# E-P-020-R1_0.net
KiCad netlist of a schematic drawn in EAGLE
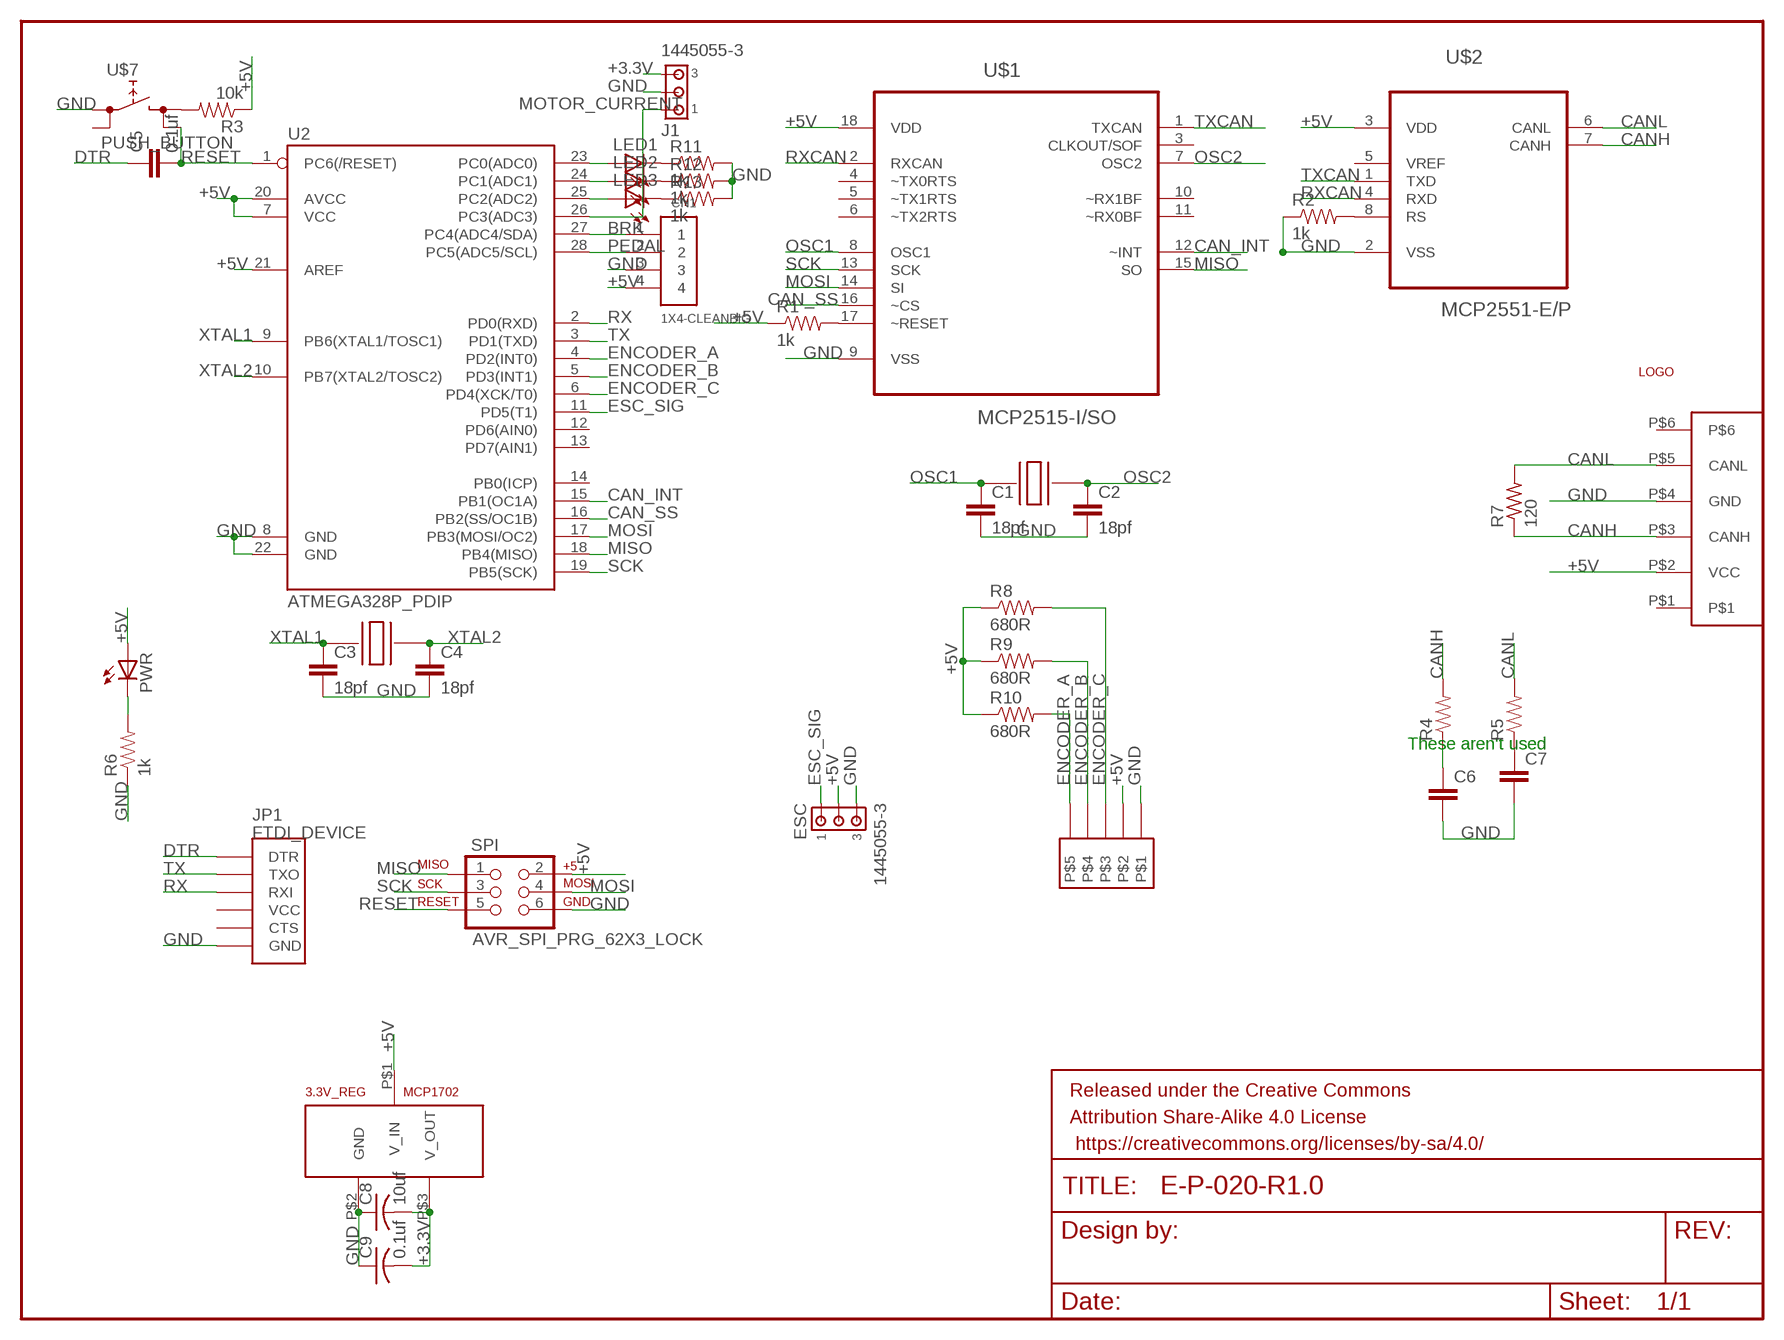
[diagram p0: schematic, sheet 1]

(export (version "E")
  (design (tool "Eeschema 10.0.6"))
  (components
    (comp (ref "3.3V_REG")
      (value "MCP1702")
      (footprint "eagle-import:SOT-23A")
      (libsource (lib "eagle-import") (part "MCP1702"))
    )
    (comp (ref "C1")
      (value "18pf")
      (footprint "eagle-import:0805")
      (libsource (lib "eagle-import") (part "CAP0805"))
    )
    (comp (ref "C2")
      (value "18pf")
      (footprint "eagle-import:0805")
      (libsource (lib "eagle-import") (part "CAP0805"))
    )
    (comp (ref "C3")
      (value "18pf")
      (footprint "eagle-import:0805")
      (libsource (lib "eagle-import") (part "CAP0805"))
    )
    (comp (ref "C4")
      (value "18pf")
      (footprint "eagle-import:0805")
      (libsource (lib "eagle-import") (part "CAP0805"))
    )
    (comp (ref "C5")
      (value "0.1uf")
      (footprint "eagle-import:0805")
      (libsource (lib "eagle-import") (part "CAP0805"))
    )
    (comp (ref "C6")
      (value "CAP0805")
      (footprint "eagle-import:0805")
      (libsource (lib "eagle-import") (part "CAP0805"))
    )
    (comp (ref "C7")
      (value "CAP0805")
      (footprint "eagle-import:0805")
      (libsource (lib "eagle-import") (part "CAP0805"))
    )
    (comp (ref "C8")
      (value "10uf")
      (footprint "eagle-import:C0805")
      (libsource (lib "eagle-import") (part "C-USC0805"))
    )
    (comp (ref "C9")
      (value "0.1uf")
      (footprint "eagle-import:C0805")
      (libsource (lib "eagle-import") (part "C-USC0805"))
    )
    (comp (ref "CAN-BUS")
      (value "CAN_6P6C")
      (footprint "eagle-import:CAN_6P6C")
      (libsource (lib "eagle-import") (part "CAN_6P6C"))
    )
    (comp (ref "CN1")
      (value "1X4-CLEANBIG")
      (footprint "eagle-import:1X04-CLEANBIG")
      (libsource (lib "eagle-import") (part "1X4-CLEANBIG"))
    )
    (comp (ref "ENCODER")
      (value "5_PIN_MICRO_MATE_N_LOCK")
      (footprint "eagle-import:5_PIN_MICRO_MATE_N_LOCK")
      (libsource (lib "eagle-import") (part "5_PIN_MICRO_MATE_N_LOCK"))
    )
    (comp (ref "ESC")
      (value "1445055-3")
      (footprint "eagle-import:1445055-3")
      (libsource (lib "eagle-import") (part "1445055-3"))
    )
    (comp (ref "FRAME1")
      (value "FRAME-LETTERNO_PACKAGE")
      (footprint "eagle-import:DUMMY")
      (fields (field (name "DESIGNER") "Nobody"))
      (libsource (lib "eagle-import") (part "FRAME-LETTERNO_PACKAGE"))
    )
    (comp (ref "J1")
      (value "1445055-3")
      (footprint "eagle-import:1445055-3")
      (libsource (lib "eagle-import") (part "1445055-3"))
    )
    (comp (ref "JP1")
      (value "FTDI_DEVICE")
      (footprint "eagle-import:FTDI_DEVICE_SIDE")
      (libsource (lib "eagle-import") (part "FTDI_DEVICE"))
    )
    (comp (ref "LED1")
      (value "LEDSMT1206")
      (footprint "eagle-import:1206")
      (libsource (lib "eagle-import") (part "adafruit_LEDSMT1206"))
    )
    (comp (ref "LED2")
      (value "LEDSMT1206")
      (footprint "eagle-import:1206")
      (libsource (lib "eagle-import") (part "adafruit_LEDSMT1206"))
    )
    (comp (ref "LED3")
      (value "LEDSMT1206")
      (footprint "eagle-import:1206")
      (libsource (lib "eagle-import") (part "adafruit_LEDSMT1206"))
    )
    (comp (ref "PWR")
      (value "LEDCHIPLED_1206")
      (footprint "eagle-import:CHIPLED_1206")
      (libsource (lib "eagle-import") (part "LEDCHIPLED_1206"))
    )
    (comp (ref "R1")
      (value "1k")
      (footprint "eagle-import:0805")
      (libsource (lib "eagle-import") (part "SparkFun-Passives_RESISTOR0805-RES"))
    )
    (comp (ref "R2")
      (value "1k")
      (footprint "eagle-import:0805")
      (libsource (lib "eagle-import") (part "SparkFun-Passives_RESISTOR0805-RES"))
    )
    (comp (ref "R3")
      (value "10k")
      (footprint "eagle-import:0805")
      (libsource (lib "eagle-import") (part "SparkFun-Passives_RESISTOR0805-RES"))
    )
    (comp (ref "R4")
      (value "RESISTOR0805-RES")
      (footprint "eagle-import:0805")
      (libsource (lib "eagle-import") (part "SparkFun-Passives_RESISTOR0805-RES"))
    )
    (comp (ref "R5")
      (value "RESISTOR0805-RES")
      (footprint "eagle-import:0805")
      (libsource (lib "eagle-import") (part "SparkFun-Passives_RESISTOR0805-RES"))
    )
    (comp (ref "R6")
      (value "1k")
      (footprint "eagle-import:0805")
      (libsource (lib "eagle-import") (part "SparkFun-Passives_RESISTOR0805-RES"))
    )
    (comp (ref "R7")
      (value "120")
      (footprint "eagle-import:M1206")
      (libsource (lib "eagle-import") (part "R-US_M1206"))
    )
    (comp (ref "R8")
      (value "680R")
      (footprint "eagle-import:0805")
      (libsource (lib "eagle-import") (part "0.75OHM-1/4W-1%(0805)"))
    )
    (comp (ref "R9")
      (value "680R")
      (footprint "eagle-import:0805")
      (libsource (lib "eagle-import") (part "0.75OHM-1/4W-1%(0805)"))
    )
    (comp (ref "R10")
      (value "680R")
      (footprint "eagle-import:0805")
      (libsource (lib "eagle-import") (part "0.75OHM-1/4W-1%(0805)"))
    )
    (comp (ref "R11")
      (value "1k")
      (footprint "eagle-import:0805")
      (libsource (lib "eagle-import") (part "RESISTOR0805-RES"))
    )
    (comp (ref "R12")
      (value "1k")
      (footprint "eagle-import:0805")
      (libsource (lib "eagle-import") (part "RESISTOR0805-RES"))
    )
    (comp (ref "R13")
      (value "1k")
      (footprint "eagle-import:0805")
      (libsource (lib "eagle-import") (part "RESISTOR0805-RES"))
    )
    (comp (ref "SPI")
      (value "AVR_SPI_PRG_62X3_LOCK")
      (footprint "eagle-import:2X3_LOCK")
      (libsource (lib "eagle-import") (part "AVR_SPI_PRG_62X3_LOCK"))
    )
    (comp (ref "U$1")
      (value "MCP2515-I/SO")
      (footprint "eagle-import:SOIC127P1034X264-18N")
      (libsource (lib "eagle-import") (part "MCP2515-I/SO"))
    )
    (comp (ref "U$2")
      (value "MCP2551-E/P")
      (footprint "eagle-import:DIP254P762X432-8")
      (libsource (lib "eagle-import") (part "MCP2551-E/P"))
    )
    (comp (ref "U$3")
      (value "CRYSTAL")
      (footprint "eagle-import:7A_CRYSTAL")
      (libsource (lib "eagle-import") (part "CRYSTAL"))
    )
    (comp (ref "U$4")
      (value "CRYSTAL")
      (footprint "eagle-import:7A_CRYSTAL")
      (libsource (lib "eagle-import") (part "CRYSTAL"))
    )
    (comp (ref "U$6")
      (value "LOGO")
      (footprint "eagle-import:LOGO")
      (libsource (lib "eagle-import") (part "LOGO"))
    )
    (comp (ref "U$7")
      (value "PUSH_BUTTON")
      (footprint "eagle-import:PUSHBUTTON")
      (libsource (lib "eagle-import") (part "PUSH_BUTTON"))
    )
    (comp (ref "U2")
      (value "ATMEGA328P_PDIP")
      (footprint "eagle-import:DIL28-3")
      (libsource (lib "eagle-import") (part "ATMEGA328P_PDIP"))
    )
  )
  (nets
    (net (code "1") (name "/+3.3V") (class "Default")
      (node (ref "3.3V_REG") (pin "P$3") (pinfunction "V_OUT_P$3") (pintype "bidirectional"))
      (node (ref "C8") (pin "2") (pinfunction "2_2") (pintype "passive"))
      (node (ref "C9") (pin "2") (pinfunction "2_2") (pintype "passive"))
      (node (ref "J1") (pin "3") (pinfunction "3_3") (pintype "passive"))
    )
    (net (code "2") (name "/+5V") (class "Default")
      (node (ref "3.3V_REG") (pin "P$1") (pinfunction "V_IN_P$1") (pintype "bidirectional"))
      (node (ref "CAN-BUS") (pin "P$2") (pinfunction "VCC_P$2") (pintype "bidirectional"))
      (node (ref "CN1") (pin "4") (pinfunction "4_4") (pintype "bidirectional"))
      (node (ref "ENCODER") (pin "P$4") (pinfunction "P$2_P$4") (pintype "bidirectional"))
      (node (ref "ESC") (pin "2") (pinfunction "2_2") (pintype "passive"))
      (node (ref "PWR") (pin "A") (pinfunction "A_A") (pintype "passive"))
      (node (ref "R1") (pin "1") (pinfunction "1_1") (pintype "passive"))
      (node (ref "R10") (pin "1") (pinfunction "1_1") (pintype "passive"))
      (node (ref "R3") (pin "1") (pinfunction "1_1") (pintype "passive"))
      (node (ref "R8") (pin "1") (pinfunction "1_1") (pintype "passive"))
      (node (ref "R9") (pin "1") (pinfunction "1_1") (pintype "passive"))
      (node (ref "SPI") (pin "2") (pinfunction "2_2") (pintype "passive"))
      (node (ref "U$1") (pin "18") (pinfunction "VDD_18") (pintype "power_in"))
      (node (ref "U$2") (pin "3") (pinfunction "VDD_3") (pintype "power_in"))
      (node (ref "U2") (pin "20") (pinfunction "AVCC_20") (pintype "bidirectional"))
      (node (ref "U2") (pin "21") (pinfunction "AREF_21") (pintype "bidirectional"))
      (node (ref "U2") (pin "7") (pinfunction "VCC_7") (pintype "bidirectional"))
    )
    (net (code "3") (name "/BRK") (class "Default")
      (node (ref "CN1") (pin "1") (pinfunction "1_1") (pintype "bidirectional"))
      (node (ref "U2") (pin "27") (pinfunction "PC4(ADC4/SDA)_27") (pintype "bidirectional"))
    )
    (net (code "4") (name "/CANH") (class "Default")
      (node (ref "CAN-BUS") (pin "P$3") (pinfunction "CANH_P$3") (pintype "bidirectional"))
      (node (ref "R4") (pin "2") (pinfunction "2_2") (pintype "passive"))
      (node (ref "R7") (pin "1") (pinfunction "1_1") (pintype "passive"))
      (node (ref "U$2") (pin "7") (pinfunction "CANH_7") (pintype "output"))
    )
    (net (code "5") (name "/CANL") (class "Default")
      (node (ref "CAN-BUS") (pin "P$5") (pinfunction "CANL_P$5") (pintype "bidirectional"))
      (node (ref "R5") (pin "2") (pinfunction "2_2") (pintype "passive"))
      (node (ref "R7") (pin "2") (pinfunction "2_2") (pintype "passive"))
      (node (ref "U$2") (pin "6") (pinfunction "CANL_6") (pintype "output"))
    )
    (net (code "6") (name "/CAN_INT") (class "Default")
      (node (ref "U$1") (pin "12") (pinfunction "~{INT}_12") (pintype "output"))
      (node (ref "U2") (pin "15") (pinfunction "PB1(OC1A)_15") (pintype "bidirectional"))
    )
    (net (code "7") (name "/CAN_SS") (class "Default")
      (node (ref "U$1") (pin "16") (pinfunction "~{CS}_16") (pintype "input"))
      (node (ref "U2") (pin "16") (pinfunction "PB2(SS/OC1B)_16") (pintype "bidirectional"))
    )
    (net (code "8") (name "/DTR") (class "Default")
      (node (ref "C5") (pin "1") (pinfunction "1_1") (pintype "passive"))
      (node (ref "JP1") (pin "P$1") (pinfunction "DTR_P$1") (pintype "bidirectional"))
    )
    (net (code "9") (name "/ENCODER_A") (class "Default")
      (node (ref "ENCODER") (pin "P$1") (pinfunction "P$5_P$1") (pintype "bidirectional"))
      (node (ref "R10") (pin "2") (pinfunction "2_2") (pintype "passive"))
      (node (ref "U2") (pin "4") (pinfunction "PD2(INT0)_4") (pintype "bidirectional"))
    )
    (net (code "10") (name "/ENCODER_B") (class "Default")
      (node (ref "ENCODER") (pin "P$2") (pinfunction "P$4_P$2") (pintype "bidirectional"))
      (node (ref "R9") (pin "2") (pinfunction "2_2") (pintype "passive"))
      (node (ref "U2") (pin "5") (pinfunction "PD3(INT1)_5") (pintype "bidirectional"))
    )
    (net (code "11") (name "/ENCODER_C") (class "Default")
      (node (ref "ENCODER") (pin "P$3") (pinfunction "P$3_P$3") (pintype "bidirectional"))
      (node (ref "R8") (pin "2") (pinfunction "2_2") (pintype "passive"))
      (node (ref "U2") (pin "6") (pinfunction "PD4(XCK/T0)_6") (pintype "bidirectional"))
    )
    (net (code "12") (name "/ESC_SIG") (class "Default")
      (node (ref "ESC") (pin "1") (pinfunction "1_1") (pintype "passive"))
      (node (ref "U2") (pin "11") (pinfunction "PD5(T1)_11") (pintype "bidirectional"))
    )
    (net (code "13") (name "/GND") (class "Default")
      (node (ref "3.3V_REG") (pin "P$2") (pinfunction "GND_P$2") (pintype "bidirectional"))
      (node (ref "C1") (pin "2") (pinfunction "2_2") (pintype "passive"))
      (node (ref "C2") (pin "2") (pinfunction "2_2") (pintype "passive"))
      (node (ref "C3") (pin "2") (pinfunction "2_2") (pintype "passive"))
      (node (ref "C4") (pin "2") (pinfunction "2_2") (pintype "passive"))
      (node (ref "C6") (pin "2") (pinfunction "2_2") (pintype "passive"))
      (node (ref "C7") (pin "2") (pinfunction "2_2") (pintype "passive"))
      (node (ref "C8") (pin "1") (pinfunction "1_1") (pintype "passive"))
      (node (ref "C9") (pin "1") (pinfunction "1_1") (pintype "passive"))
      (node (ref "CAN-BUS") (pin "P$4") (pinfunction "GND_P$4") (pintype "bidirectional"))
      (node (ref "CN1") (pin "3") (pinfunction "3_3") (pintype "bidirectional"))
      (node (ref "ENCODER") (pin "P$5") (pinfunction "P$1_P$5") (pintype "bidirectional"))
      (node (ref "ESC") (pin "3") (pinfunction "3_3") (pintype "passive"))
      (node (ref "J1") (pin "2") (pinfunction "2_2") (pintype "passive"))
      (node (ref "JP1") (pin "P$6") (pinfunction "GND_P$6") (pintype "bidirectional"))
      (node (ref "R11") (pin "2") (pinfunction "2_2") (pintype "passive"))
      (node (ref "R12") (pin "2") (pinfunction "2_2") (pintype "passive"))
      (node (ref "R13") (pin "2") (pinfunction "2_2") (pintype "passive"))
      (node (ref "R2") (pin "1") (pinfunction "1_1") (pintype "passive"))
      (node (ref "R6") (pin "1") (pinfunction "1_1") (pintype "passive"))
      (node (ref "SPI") (pin "6") (pinfunction "6_6") (pintype "passive"))
      (node (ref "U$1") (pin "9") (pinfunction "VSS_9") (pintype "power_in"))
      (node (ref "U$2") (pin "2") (pinfunction "VSS_2") (pintype "passive"))
      (node (ref "U$7") (pin "L1") (pinfunction "L_L1") (pintype "passive"))
      (node (ref "U2") (pin "22") (pinfunction "GND_22") (pintype "bidirectional"))
      (node (ref "U2") (pin "8") (pinfunction "GND_8") (pintype "bidirectional"))
    )
    (net (code "14") (name "/MISO") (class "Default")
      (node (ref "SPI") (pin "1") (pinfunction "1_1") (pintype "passive"))
      (node (ref "U$1") (pin "15") (pinfunction "SO_15") (pintype "output"))
      (node (ref "U2") (pin "18") (pinfunction "PB4(MISO)_18") (pintype "bidirectional"))
    )
    (net (code "15") (name "/MOSI") (class "Default")
      (node (ref "SPI") (pin "4") (pinfunction "4_4") (pintype "passive"))
      (node (ref "U$1") (pin "14") (pinfunction "SI_14") (pintype "input"))
      (node (ref "U2") (pin "17") (pinfunction "PB3(MOSI/OC2)_17") (pintype "bidirectional"))
    )
    (net (code "16") (name "/MOTOR_CURRENT") (class "Default")
      (node (ref "J1") (pin "1") (pinfunction "1_1") (pintype "passive"))
      (node (ref "U2") (pin "26") (pinfunction "PC3(ADC3)_26") (pintype "bidirectional"))
    )
    (net (code "17") (name "/OSC1") (class "Default")
      (node (ref "C1") (pin "1") (pinfunction "1_1") (pintype "passive"))
      (node (ref "U$1") (pin "8") (pinfunction "OSC1_8") (pintype "input"))
      (node (ref "U$3") (pin "P$2") (pinfunction "P$2_P$2") (pintype "bidirectional"))
    )
    (net (code "18") (name "/OSC2") (class "Default")
      (node (ref "C2") (pin "1") (pinfunction "1_1") (pintype "passive"))
      (node (ref "U$1") (pin "7") (pinfunction "OSC2_7") (pintype "output"))
      (node (ref "U$3") (pin "P$1") (pinfunction "P$1_P$1") (pintype "bidirectional"))
    )
    (net (code "19") (name "/PEDAL") (class "Default")
      (node (ref "CN1") (pin "2") (pinfunction "2_2") (pintype "bidirectional"))
      (node (ref "U2") (pin "28") (pinfunction "PC5(ADC5/SCL)_28") (pintype "bidirectional"))
    )
    (net (code "20") (name "/RESET") (class "Default")
      (node (ref "C5") (pin "2") (pinfunction "2_2") (pintype "passive"))
      (node (ref "SPI") (pin "5") (pinfunction "5_5") (pintype "passive"))
      (node (ref "U$7") (pin "R2") (pinfunction "R_R2") (pintype "passive"))
      (node (ref "U2") (pin "1") (pinfunction "PC6(/RESET)_1") (pintype "bidirectional"))
    )
    (net (code "21") (name "/RX") (class "Default")
      (node (ref "JP1") (pin "P$3") (pinfunction "RXI_P$3") (pintype "bidirectional"))
      (node (ref "U2") (pin "2") (pinfunction "PD0(RXD)_2") (pintype "bidirectional"))
    )
    (net (code "22") (name "/RXCAN") (class "Default")
      (node (ref "U$1") (pin "2") (pinfunction "RXCAN_2") (pintype "input"))
      (node (ref "U$2") (pin "4") (pinfunction "RXD_4") (pintype "input"))
    )
    (net (code "23") (name "/SCK") (class "Default")
      (node (ref "SPI") (pin "3") (pinfunction "3_3") (pintype "passive"))
      (node (ref "U$1") (pin "13") (pinfunction "SCK_13") (pintype "input"))
      (node (ref "U2") (pin "19") (pinfunction "PB5(SCK)_19") (pintype "bidirectional"))
    )
    (net (code "24") (name "/TX") (class "Default")
      (node (ref "JP1") (pin "P$2") (pinfunction "TXO_P$2") (pintype "bidirectional"))
      (node (ref "U2") (pin "3") (pinfunction "PD1(TXD)_3") (pintype "bidirectional"))
    )
    (net (code "25") (name "/TXCAN") (class "Default")
      (node (ref "U$1") (pin "1") (pinfunction "TXCAN_1") (pintype "output"))
      (node (ref "U$2") (pin "1") (pinfunction "TXD_1") (pintype "input"))
    )
    (net (code "26") (name "/XTAL1") (class "Default")
      (node (ref "C3") (pin "1") (pinfunction "1_1") (pintype "passive"))
      (node (ref "U$4") (pin "P$2") (pinfunction "P$2_P$2") (pintype "bidirectional"))
      (node (ref "U2") (pin "9") (pinfunction "PB6(XTAL1/TOSC1)_9") (pintype "bidirectional"))
    )
    (net (code "27") (name "/XTAL2") (class "Default")
      (node (ref "C4") (pin "1") (pinfunction "1_1") (pintype "passive"))
      (node (ref "U$4") (pin "P$1") (pinfunction "P$1_P$1") (pintype "bidirectional"))
      (node (ref "U2") (pin "10") (pinfunction "PB7(XTAL2/TOSC2)_10") (pintype "bidirectional"))
    )
    (net (code "28") (name "Net-(C6-Pad1)") (class "Default")
      (node (ref "C6") (pin "1") (pinfunction "1_1") (pintype "passive"))
      (node (ref "R4") (pin "1") (pinfunction "1_1") (pintype "passive"))
    )
    (net (code "29") (name "Net-(C7-Pad1)") (class "Default")
      (node (ref "C7") (pin "1") (pinfunction "1_1") (pintype "passive"))
      (node (ref "R5") (pin "1") (pinfunction "1_1") (pintype "passive"))
    )
    (net (code "30") (name "Net-(LED1-PadC)") (class "Default")
      (node (ref "LED1") (pin "C") (pinfunction "C_C") (pintype "passive"))
      (node (ref "R11") (pin "1") (pinfunction "1_1") (pintype "passive"))
    )
    (net (code "31") (name "Net-(LED2-PadC)") (class "Default")
      (node (ref "LED2") (pin "C") (pinfunction "C_C") (pintype "passive"))
      (node (ref "R12") (pin "1") (pinfunction "1_1") (pintype "passive"))
    )
    (net (code "32") (name "Net-(LED3-PadC)") (class "Default")
      (node (ref "LED3") (pin "C") (pinfunction "C_C") (pintype "passive"))
      (node (ref "R13") (pin "1") (pinfunction "1_1") (pintype "passive"))
    )
    (net (code "33") (name "Net-(PWR-PadC)") (class "Default")
      (node (ref "PWR") (pin "C") (pinfunction "C_C") (pintype "passive"))
      (node (ref "R6") (pin "2") (pinfunction "2_2") (pintype "passive"))
    )
    (net (code "34") (name "Net-(R3-Pad2)") (class "Default")
      (node (ref "R3") (pin "2") (pinfunction "2_2") (pintype "passive"))
      (node (ref "U$7") (pin "R1") (pinfunction "R_R1") (pintype "passive"))
    )
    (net (code "35") (name "Net-(U$1-~{RESET})") (class "Default")
      (node (ref "R1") (pin "2") (pinfunction "2_2") (pintype "passive"))
      (node (ref "U$1") (pin "17") (pinfunction "~{RESET}_17") (pintype "input"))
    )
    (net (code "36") (name "Net-(U$2-RS)") (class "Default")
      (node (ref "R2") (pin "2") (pinfunction "2_2") (pintype "passive"))
      (node (ref "U$2") (pin "8") (pinfunction "RS_8") (pintype "input"))
    )
    (net (code "37") (name "Net-(U2-PC0(ADC0))") (class "Default")
      (node (ref "LED1") (pin "A") (pinfunction "A_A") (pintype "passive"))
      (node (ref "U2") (pin "23") (pinfunction "PC0(ADC0)_23") (pintype "bidirectional"))
    )
    (net (code "38") (name "Net-(U2-PC1(ADC1))") (class "Default")
      (node (ref "LED2") (pin "A") (pinfunction "A_A") (pintype "passive"))
      (node (ref "U2") (pin "24") (pinfunction "PC1(ADC1)_24") (pintype "bidirectional"))
    )
    (net (code "39") (name "Net-(U2-PC2(ADC2))") (class "Default")
      (node (ref "LED3") (pin "A") (pinfunction "A_A") (pintype "passive"))
      (node (ref "U2") (pin "25") (pinfunction "PC2(ADC2)_25") (pintype "bidirectional"))
    )
    (net (code "40") (name "unconnected-(CAN-BUS-PadP$1)") (class "Default")
      (node (ref "CAN-BUS") (pin "P$1") (pinfunction "P$1_P$1") (pintype "bidirectional"))
    )
    (net (code "41") (name "unconnected-(CAN-BUS-PadP$6)") (class "Default")
      (node (ref "CAN-BUS") (pin "P$6") (pinfunction "P$6_P$6") (pintype "bidirectional"))
    )
    (net (code "42") (name "unconnected-(JP1-CTS-PadP$5)") (class "Default")
      (node (ref "JP1") (pin "P$5") (pinfunction "CTS_P$5") (pintype "bidirectional"))
    )
    (net (code "43") (name "unconnected-(JP1-VCC-PadP$4)") (class "Default")
      (node (ref "JP1") (pin "P$4") (pinfunction "VCC_P$4") (pintype "bidirectional"))
    )
    (net (code "44") (name "unconnected-(U$1-CLKOUT{slash}SOF-Pad3)") (class "Default")
      (node (ref "U$1") (pin "3") (pinfunction "CLKOUT/SOF_3") (pintype "output"))
    )
    (net (code "45") (name "unconnected-(U$1-~{RX0BF}-Pad11)") (class "Default")
      (node (ref "U$1") (pin "11") (pinfunction "~{RX0BF}_11") (pintype "output"))
    )
    (net (code "46") (name "unconnected-(U$1-~{RX1BF}-Pad10)") (class "Default")
      (node (ref "U$1") (pin "10") (pinfunction "~{RX1BF}_10") (pintype "output"))
    )
    (net (code "47") (name "unconnected-(U$1-~{TX0RTS}-Pad4)") (class "Default")
      (node (ref "U$1") (pin "4") (pinfunction "~{TX0RTS}_4") (pintype "input"))
    )
    (net (code "48") (name "unconnected-(U$1-~{TX1RTS}-Pad5)") (class "Default")
      (node (ref "U$1") (pin "5") (pinfunction "~{TX1RTS}_5") (pintype "input"))
    )
    (net (code "49") (name "unconnected-(U$1-~{TX2RTS}-Pad6)") (class "Default")
      (node (ref "U$1") (pin "6") (pinfunction "~{TX2RTS}_6") (pintype "input"))
    )
    (net (code "50") (name "unconnected-(U$2-VREF-Pad5)") (class "Default")
      (node (ref "U$2") (pin "5") (pinfunction "VREF_5") (pintype "input"))
    )
    (net (code "51") (name "unconnected-(U$7-L-PadL2)") (class "Default")
      (node (ref "U$7") (pin "L2") (pinfunction "L_L2") (pintype "passive"))
    )
    (net (code "52") (name "unconnected-(U2-PB0(ICP)-Pad14)") (class "Default")
      (node (ref "U2") (pin "14") (pinfunction "PB0(ICP)_14") (pintype "bidirectional"))
    )
    (net (code "53") (name "unconnected-(U2-PD6(AIN0)-Pad12)") (class "Default")
      (node (ref "U2") (pin "12") (pinfunction "PD6(AIN0)_12") (pintype "bidirectional"))
    )
    (net (code "54") (name "unconnected-(U2-PD7(AIN1)-Pad13)") (class "Default")
      (node (ref "U2") (pin "13") (pinfunction "PD7(AIN1)_13") (pintype "bidirectional"))
    )
  )
)
